# 2331new.net
KiCad netlist of a schematic drawn in Altium Designer
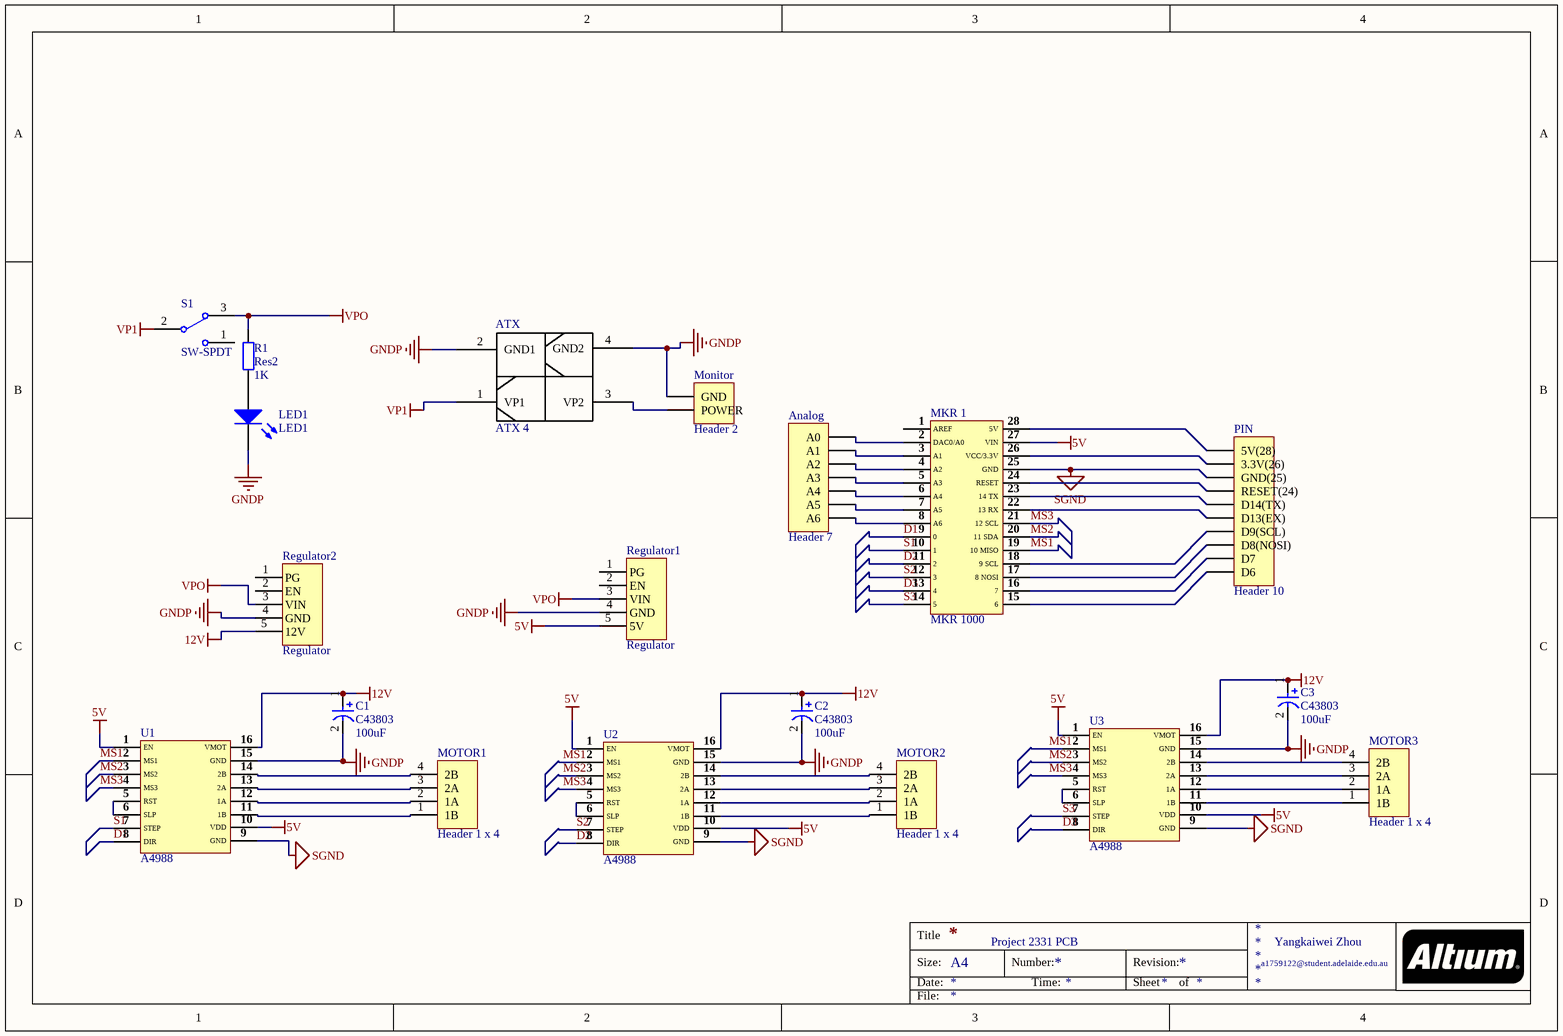
[diagram p0: 2331new.SchDoc]

(export (version "E")
  (design (tool "Eeschema 10.0.6"))
  (components
    (comp (ref "Analog")
      (value "Header 7")
      (footprint "HDR1X7")
      (description "Header, 7-Pin")
      (fields (field (name "PUBLISHER") "Altium Limited"))
      (libsource (lib "Miscellaneous Connectors") (part "Header 7"))
    )
    (comp (ref "ATX")
      (value "ATX 4")
      (footprint "ATX4")
      (description "ATX 4Pins power connector")
      (libsource (lib "CNC_shield_for_mkr1000_SchLib") (part "ATX 4"))
    )
    (comp (ref "C1")
      (value "C43803")
      (footprint "C43803")
      (description "Polarized Capacitor C43803 100uF")
      (fields (field (name "ALTIUM_VALUE") "100uF") (field (name "PUBLISHER") "Altium Limited"))
      (libsource (lib "CNC_shield_for_mkr1000_SchLib") (part "C43803"))
    )
    (comp (ref "C2")
      (value "C43803")
      (footprint "C43803")
      (description "Polarized Capacitor C43803 100uF")
      (fields (field (name "ALTIUM_VALUE") "100uF") (field (name "PUBLISHER") "Altium Limited"))
      (libsource (lib "CNC_shield_for_mkr1000_SchLib") (part "C43803"))
    )
    (comp (ref "C3")
      (value "C43803")
      (footprint "C43803")
      (description "Polarized Capacitor C43803 100uF")
      (fields (field (name "ALTIUM_VALUE") "100uF") (field (name "PUBLISHER") "Altium Limited"))
      (libsource (lib "CNC_shield_for_mkr1000_SchLib") (part "C43803"))
    )
    (comp (ref "LED1")
      (value "LED1")
      (footprint "LED")
      (description "Typical RED GaAs LED")
      (fields (field (name "PUBLISHER") "Altium Limited"))
      (libsource (lib "Miscellaneous Devices") (part "LED1"))
    )
    (comp (ref "MKR 1")
      (value "MKR 1000")
      (footprint "MKR1000")
      (description "Arduino wifi")
      (libsource (lib "altium-import") (part "root_0_Arduino MKR 1000_"))
    )
    (comp (ref "Monitor")
      (value "Header 2")
      (footprint "HDR1X2")
      (description "Header, 2-Pin")
      (fields (field (name "PUBLISHER") "Altium Limited"))
      (libsource (lib "Miscellaneous Connectors") (part "Header 2"))
    )
    (comp (ref "MOTOR1")
      (value "Header 1 x 4")
      (footprint "HDR1X4")
      (description "Header, 4-Pin")
      (fields (field (name "PUBLISHER") "Altium Limited"))
      (libsource (lib "CNC_shield_for_mkr1000_SchLib") (part "Header 1 x 4"))
    )
    (comp (ref "MOTOR2")
      (value "Header 1 x 4")
      (footprint "HDR1X4")
      (description "Header, 4-Pin")
      (fields (field (name "PUBLISHER") "Altium Limited"))
      (libsource (lib "CNC_shield_for_mkr1000_SchLib") (part "Header 1 x 4"))
    )
    (comp (ref "MOTOR3")
      (value "Header 1 x 4")
      (footprint "HDR1X4")
      (description "Header, 4-Pin")
      (fields (field (name "PUBLISHER") "Altium Limited"))
      (libsource (lib "CNC_shield_for_mkr1000_SchLib") (part "Header 1 x 4"))
    )
    (comp (ref "PIN")
      (value "Header 10")
      (footprint "HDR1X10")
      (description "Header, 10-Pin")
      (fields (field (name "PUBLISHER") "Altium Limited"))
      (libsource (lib "Miscellaneous Connectors") (part "Header 10"))
    )
    (comp (ref "R1")
      (value "Res2")
      (footprint "AXIAL-0.4")
      (description "Resistor")
      (fields (field (name "ALTIUM_VALUE") "1K") (field (name "PUBLISHER") "Altium Limited"))
      (libsource (lib "Miscellaneous Devices") (part "Res2"))
    )
    (comp (ref "Regulator1")
      (value "Regulator")
      (footprint "HDR1X5")
      (description "Voltage Regulator D24V25F5")
      (fields (field (name "PUBLISHER") "Altium Limited"))
      (libsource (lib "CNC_shield_for_mkr1000_SchLib") (part "Header1x5"))
    )
    (comp (ref "Regulator2")
      (value "Regulator")
      (footprint "HDR1X5")
      (description "Voltage Regulator D24V25F5")
      (fields (field (name "PUBLISHER") "Altium Limited"))
      (libsource (lib "CNC_shield_for_mkr1000_SchLib") (part "Header1x5"))
    )
    (comp (ref "S1")
      (value "SW-SPDT")
      (footprint "SPDT")
      (description "SPDT Subminiature Toggle Switch, Right Angle Mounting, Vertical Actuation")
      (fields (field (name "PUBLISHER") "Altium Limited"))
      (libsource (lib "Miscellaneous Devices") (part "SW-SPDT"))
    )
    (comp (ref "U1")
      (value "A4988")
      (footprint "A4988 Driver")
      (description "Motor Driver")
      (libsource (lib "CNC_shield_for_mkr1000_SchLib") (part "A4988 Driver"))
    )
    (comp (ref "U2")
      (value "A4988")
      (footprint "A4988 Driver")
      (description "Motor Driver")
      (libsource (lib "CNC_shield_for_mkr1000_SchLib") (part "A4988 Driver"))
    )
    (comp (ref "U3")
      (value "A4988")
      (footprint "A4988 Driver")
      (description "Motor Driver")
      (libsource (lib "CNC_shield_for_mkr1000_SchLib") (part "A4988 Driver"))
    )
  )
  (nets
    (net (code "2") (name "/D1") (class "Default")
      (node (ref "MKR 1") (pin "9") (pinfunction "0_9") (pintype "passive"))
      (node (ref "U1") (pin "8") (pinfunction "DIR_8") (pintype "passive"))
    )
    (net (code "3") (name "/D2") (class "Default")
      (node (ref "MKR 1") (pin "11") (pinfunction "2_11") (pintype "passive"))
      (node (ref "U2") (pin "8") (pinfunction "DIR_8") (pintype "passive"))
    )
    (net (code "4") (name "/D3") (class "Default")
      (node (ref "MKR 1") (pin "13") (pinfunction "4_13") (pintype "passive"))
      (node (ref "U3") (pin "8") (pinfunction "DIR_8") (pintype "passive"))
    )
    (net (code "5") (name "/MS1") (class "Default")
      (node (ref "MKR 1") (pin "19") (pinfunction "10_MISO_19") (pintype "passive"))
      (node (ref "U1") (pin "2") (pinfunction "MS1_2") (pintype "passive"))
      (node (ref "U2") (pin "2") (pinfunction "MS1_2") (pintype "passive"))
      (node (ref "U3") (pin "2") (pinfunction "MS1_2") (pintype "passive"))
    )
    (net (code "6") (name "/MS2") (class "Default")
      (node (ref "MKR 1") (pin "20") (pinfunction "11_SDA_20") (pintype "passive"))
      (node (ref "U1") (pin "3") (pinfunction "MS2_3") (pintype "passive"))
      (node (ref "U2") (pin "3") (pinfunction "MS2_3") (pintype "passive"))
      (node (ref "U3") (pin "3") (pinfunction "MS2_3") (pintype "passive"))
    )
    (net (code "7") (name "/MS3") (class "Default")
      (node (ref "MKR 1") (pin "21") (pinfunction "12_SCL_21") (pintype "passive"))
      (node (ref "U1") (pin "4") (pinfunction "MS3_4") (pintype "passive"))
      (node (ref "U2") (pin "4") (pinfunction "MS3_4") (pintype "passive"))
      (node (ref "U3") (pin "4") (pinfunction "MS3_4") (pintype "passive"))
    )
    (net (code "8") (name "/S1") (class "Default")
      (node (ref "MKR 1") (pin "10") (pinfunction "1_10") (pintype "passive"))
      (node (ref "U1") (pin "7") (pinfunction "STEP_7") (pintype "passive"))
    )
    (net (code "9") (name "/S2") (class "Default")
      (node (ref "MKR 1") (pin "12") (pinfunction "3_12") (pintype "passive"))
      (node (ref "U2") (pin "7") (pinfunction "STEP_7") (pintype "passive"))
    )
    (net (code "10") (name "/S3") (class "Default")
      (node (ref "MKR 1") (pin "14") (pinfunction "5_14") (pintype "passive"))
      (node (ref "U3") (pin "7") (pinfunction "STEP_7") (pintype "passive"))
    )
    (net (code "11") (name "5V") (class "Default")
      (node (ref "MKR 1") (pin "27") (pinfunction "VIN_27") (pintype "passive"))
      (node (ref "Regulator1") (pin "5") (pinfunction "12V_5") (pintype "passive"))
      (node (ref "U1") (pin "1") (pinfunction "EN_1") (pintype "passive"))
      (node (ref "U1") (pin "10") (pinfunction "VDD_10") (pintype "passive"))
      (node (ref "U2") (pin "1") (pinfunction "EN_1") (pintype "passive"))
      (node (ref "U2") (pin "10") (pinfunction "VDD_10") (pintype "passive"))
      (node (ref "U3") (pin "1") (pinfunction "EN_1") (pintype "passive"))
      (node (ref "U3") (pin "10") (pinfunction "VDD_10") (pintype "passive"))
    )
    (net (code "12") (name "12V") (class "Default")
      (node (ref "C1") (pin "1") (pinfunction "1_1") (pintype "passive"))
      (node (ref "C2") (pin "1") (pinfunction "1_1") (pintype "passive"))
      (node (ref "C3") (pin "1") (pinfunction "1_1") (pintype "passive"))
      (node (ref "Regulator2") (pin "5") (pinfunction "12V_5") (pintype "passive"))
      (node (ref "U1") (pin "16") (pinfunction "VMOT_16") (pintype "passive"))
      (node (ref "U2") (pin "16") (pinfunction "VMOT_16") (pintype "passive"))
      (node (ref "U3") (pin "16") (pinfunction "VMOT_16") (pintype "passive"))
    )
    (net (code "13") (name "GNDP") (class "Default")
      (node (ref "ATX") (pin "2") (pinfunction "GND1_2") (pintype "passive"))
      (node (ref "ATX") (pin "4") (pinfunction "GND2_4") (pintype "passive"))
      (node (ref "C1") (pin "2") (pinfunction "2_2") (pintype "passive"))
      (node (ref "C2") (pin "2") (pinfunction "2_2") (pintype "passive"))
      (node (ref "C3") (pin "2") (pinfunction "2_2") (pintype "passive"))
      (node (ref "LED1") (pin "2") (pinfunction "K_2") (pintype "passive"))
      (node (ref "Monitor") (pin "1") (pinfunction "GND_1") (pintype "passive"))
      (node (ref "Regulator1") (pin "4") (pinfunction "GND_4") (pintype "passive"))
      (node (ref "Regulator2") (pin "4") (pinfunction "GND_4") (pintype "passive"))
      (node (ref "U1") (pin "15") (pinfunction "GND_15") (pintype "passive"))
      (node (ref "U2") (pin "15") (pinfunction "GND_15") (pintype "passive"))
      (node (ref "U3") (pin "15") (pinfunction "GND_15") (pintype "passive"))
    )
    (net (code "14") (name "Net-(ATX-VP2)") (class "Default")
      (node (ref "ATX") (pin "3") (pinfunction "VP2_3") (pintype "passive"))
      (node (ref "Monitor") (pin "2") (pinfunction "POWER_2") (pintype "passive"))
    )
    (net (code "15") (name "Net-(Analog-A0)") (class "Default")
      (node (ref "Analog") (pin "7") (pinfunction "A0_7") (pintype "passive"))
      (node (ref "MKR 1") (pin "2") (pinfunction "DAC0/A0_2") (pintype "passive"))
    )
    (net (code "16") (name "Net-(Analog-A1)") (class "Default")
      (node (ref "Analog") (pin "6") (pinfunction "A1_6") (pintype "passive"))
      (node (ref "MKR 1") (pin "3") (pinfunction "A1_3") (pintype "passive"))
    )
    (net (code "17") (name "Net-(Analog-A2)") (class "Default")
      (node (ref "Analog") (pin "5") (pinfunction "A2_5") (pintype "passive"))
      (node (ref "MKR 1") (pin "4") (pinfunction "A2_4") (pintype "passive"))
    )
    (net (code "18") (name "Net-(Analog-A3)") (class "Default")
      (node (ref "Analog") (pin "4") (pinfunction "A3_4") (pintype "passive"))
      (node (ref "MKR 1") (pin "5") (pinfunction "A3_5") (pintype "passive"))
    )
    (net (code "19") (name "Net-(Analog-A4)") (class "Default")
      (node (ref "Analog") (pin "3") (pinfunction "A4_3") (pintype "passive"))
      (node (ref "MKR 1") (pin "6") (pinfunction "A4_6") (pintype "passive"))
    )
    (net (code "20") (name "Net-(Analog-A5)") (class "Default")
      (node (ref "Analog") (pin "2") (pinfunction "A5_2") (pintype "passive"))
      (node (ref "MKR 1") (pin "7") (pinfunction "A5_7") (pintype "passive"))
    )
    (net (code "21") (name "Net-(Analog-A6)") (class "Default")
      (node (ref "Analog") (pin "1") (pinfunction "A6_1") (pintype "passive"))
      (node (ref "MKR 1") (pin "8") (pinfunction "A6_8") (pintype "passive"))
    )
    (net (code "22") (name "Net-(LED1-A)") (class "Default")
      (node (ref "LED1") (pin "1") (pinfunction "A_1") (pintype "passive"))
      (node (ref "R1") (pin "1") (pinfunction "1_1") (pintype "passive"))
    )
    (net (code "23") (name "Net-(MKR 1-5V)") (class "Default")
      (node (ref "MKR 1") (pin "28") (pinfunction "5V_28") (pintype "passive"))
      (node (ref "PIN") (pin "1") (pinfunction "5V(28)_1") (pintype "passive"))
    )
    (net (code "24") (name "Net-(MKR 1-6)") (class "Default")
      (node (ref "MKR 1") (pin "15") (pinfunction "6_15") (pintype "passive"))
      (node (ref "PIN") (pin "10") (pinfunction "D6_10") (pintype "passive"))
    )
    (net (code "25") (name "Net-(MKR 1-7)") (class "Default")
      (node (ref "MKR 1") (pin "16") (pinfunction "7_16") (pintype "passive"))
      (node (ref "PIN") (pin "9") (pinfunction "D7_9") (pintype "passive"))
    )
    (net (code "26") (name "Net-(MKR 1-8_NOSI)") (class "Default")
      (node (ref "MKR 1") (pin "17") (pinfunction "8_NOSI_17") (pintype "passive"))
      (node (ref "PIN") (pin "8") (pinfunction "D8(NOSI)_8") (pintype "passive"))
    )
    (net (code "27") (name "Net-(MKR 1-9_SCL)") (class "Default")
      (node (ref "MKR 1") (pin "18") (pinfunction "9_SCL_18") (pintype "passive"))
      (node (ref "PIN") (pin "7") (pinfunction "D9(SCL)_7") (pintype "passive"))
    )
    (net (code "28") (name "Net-(MKR 1-13_RX)") (class "Default")
      (node (ref "MKR 1") (pin "22") (pinfunction "13_RX_22") (pintype "passive"))
      (node (ref "PIN") (pin "6") (pinfunction "D13(EX)_6") (pintype "passive"))
    )
    (net (code "29") (name "Net-(MKR 1-14_TX)") (class "Default")
      (node (ref "MKR 1") (pin "23") (pinfunction "14_TX_23") (pintype "passive"))
      (node (ref "PIN") (pin "5") (pinfunction "D14(TX)_5") (pintype "passive"))
    )
    (net (code "30") (name "Net-(MKR 1-RESET)") (class "Default")
      (node (ref "MKR 1") (pin "24") (pinfunction "RESET_24") (pintype "passive"))
      (node (ref "PIN") (pin "4") (pinfunction "RESET(24)_4") (pintype "passive"))
    )
    (net (code "31") (name "Net-(MKR 1-VCC{slash}3.3V)") (class "Default")
      (node (ref "MKR 1") (pin "26") (pinfunction "VCC/3.3V_26") (pintype "passive"))
      (node (ref "PIN") (pin "2") (pinfunction "3.3V(26)_2") (pintype "passive"))
    )
    (net (code "32") (name "Net-(MOTOR1-1A)") (class "Default")
      (node (ref "MOTOR1") (pin "2") (pinfunction "1A_2") (pintype "passive"))
      (node (ref "U1") (pin "12") (pinfunction "1A_12") (pintype "passive"))
    )
    (net (code "33") (name "Net-(MOTOR1-1B)") (class "Default")
      (node (ref "MOTOR1") (pin "1") (pinfunction "1B_1") (pintype "passive"))
      (node (ref "U1") (pin "11") (pinfunction "1B_11") (pintype "passive"))
    )
    (net (code "34") (name "Net-(MOTOR1-2A)") (class "Default")
      (node (ref "MOTOR1") (pin "3") (pinfunction "2A_3") (pintype "passive"))
      (node (ref "U1") (pin "13") (pinfunction "2A_13") (pintype "passive"))
    )
    (net (code "35") (name "Net-(MOTOR1-2B)") (class "Default")
      (node (ref "MOTOR1") (pin "4") (pinfunction "2B_4") (pintype "passive"))
      (node (ref "U1") (pin "14") (pinfunction "2B_14") (pintype "passive"))
    )
    (net (code "36") (name "Net-(MOTOR2-1A)") (class "Default")
      (node (ref "MOTOR2") (pin "2") (pinfunction "1A_2") (pintype "passive"))
      (node (ref "U2") (pin "12") (pinfunction "1A_12") (pintype "passive"))
    )
    (net (code "37") (name "Net-(MOTOR2-1B)") (class "Default")
      (node (ref "MOTOR2") (pin "1") (pinfunction "1B_1") (pintype "passive"))
      (node (ref "U2") (pin "11") (pinfunction "1B_11") (pintype "passive"))
    )
    (net (code "38") (name "Net-(MOTOR2-2A)") (class "Default")
      (node (ref "MOTOR2") (pin "3") (pinfunction "2A_3") (pintype "passive"))
      (node (ref "U2") (pin "13") (pinfunction "2A_13") (pintype "passive"))
    )
    (net (code "39") (name "Net-(MOTOR2-2B)") (class "Default")
      (node (ref "MOTOR2") (pin "4") (pinfunction "2B_4") (pintype "passive"))
      (node (ref "U2") (pin "14") (pinfunction "2B_14") (pintype "passive"))
    )
    (net (code "40") (name "Net-(MOTOR3-1A)") (class "Default")
      (node (ref "MOTOR3") (pin "2") (pinfunction "1A_2") (pintype "passive"))
      (node (ref "U3") (pin "12") (pinfunction "1A_12") (pintype "passive"))
    )
    (net (code "41") (name "Net-(MOTOR3-1B)") (class "Default")
      (node (ref "MOTOR3") (pin "1") (pinfunction "1B_1") (pintype "passive"))
      (node (ref "U3") (pin "11") (pinfunction "1B_11") (pintype "passive"))
    )
    (net (code "42") (name "Net-(MOTOR3-2A)") (class "Default")
      (node (ref "MOTOR3") (pin "3") (pinfunction "2A_3") (pintype "passive"))
      (node (ref "U3") (pin "13") (pinfunction "2A_13") (pintype "passive"))
    )
    (net (code "43") (name "Net-(MOTOR3-2B)") (class "Default")
      (node (ref "MOTOR3") (pin "4") (pinfunction "2B_4") (pintype "passive"))
      (node (ref "U3") (pin "14") (pinfunction "2B_14") (pintype "passive"))
    )
    (net (code "44") (name "Net-(U1-RST)") (class "Default")
      (node (ref "U1") (pin "5") (pinfunction "RST_5") (pintype "passive"))
      (node (ref "U1") (pin "6") (pinfunction "SLP_6") (pintype "passive"))
    )
    (net (code "45") (name "Net-(U2-RST)") (class "Default")
      (node (ref "U2") (pin "5") (pinfunction "RST_5") (pintype "passive"))
      (node (ref "U2") (pin "6") (pinfunction "SLP_6") (pintype "passive"))
    )
    (net (code "46") (name "Net-(U3-RST)") (class "Default")
      (node (ref "U3") (pin "5") (pinfunction "RST_5") (pintype "passive"))
      (node (ref "U3") (pin "6") (pinfunction "SLP_6") (pintype "passive"))
    )
    (net (code "47") (name "SGND") (class "Default")
      (node (ref "MKR 1") (pin "25") (pinfunction "GND_25") (pintype "passive"))
      (node (ref "PIN") (pin "3") (pinfunction "GND(25)_3") (pintype "passive"))
      (node (ref "U1") (pin "9") (pinfunction "GND_9") (pintype "passive"))
      (node (ref "U2") (pin "9") (pinfunction "GND_9") (pintype "passive"))
      (node (ref "U3") (pin "9") (pinfunction "GND_9") (pintype "passive"))
    )
    (net (code "48") (name "VP1") (class "Default")
      (node (ref "ATX") (pin "1") (pinfunction "VP1_1") (pintype "passive"))
      (node (ref "S1") (pin "2") (pinfunction "2_2") (pintype "passive"))
    )
    (net (code "49") (name "VPO") (class "Default")
      (node (ref "R1") (pin "2") (pinfunction "2_2") (pintype "passive"))
      (node (ref "Regulator1") (pin "3") (pinfunction "VIN_3") (pintype "passive"))
      (node (ref "Regulator2") (pin "3") (pinfunction "VIN_3") (pintype "passive"))
      (node (ref "S1") (pin "3") (pinfunction "3_3") (pintype "passive"))
    )
    (net (code "50") (name "unconnected-(MKR 1-AREF-Pad1)") (class "Default")
      (node (ref "MKR 1") (pin "1") (pinfunction "AREF_1") (pintype "passive"))
    )
    (net (code "51") (name "unconnected-(Regulator1-EN-Pad2)") (class "Default")
      (node (ref "Regulator1") (pin "2") (pinfunction "EN_2") (pintype "passive"))
    )
    (net (code "52") (name "unconnected-(Regulator1-PG-Pad1)") (class "Default")
      (node (ref "Regulator1") (pin "1") (pinfunction "PG_1") (pintype "passive"))
    )
    (net (code "53") (name "unconnected-(Regulator2-EN-Pad2)") (class "Default")
      (node (ref "Regulator2") (pin "2") (pinfunction "EN_2") (pintype "passive"))
    )
    (net (code "54") (name "unconnected-(Regulator2-PG-Pad1)") (class "Default")
      (node (ref "Regulator2") (pin "1") (pinfunction "PG_1") (pintype "passive"))
    )
    (net (code "55") (name "unconnected-(S1-Pad1)") (class "Default")
      (node (ref "S1") (pin "1") (pinfunction "1_1") (pintype "passive"))
    )
  )
)
